# Dispenser_Scale_Feedback.net
KiCad netlist of a schematic drawn in EasyEDA Pro
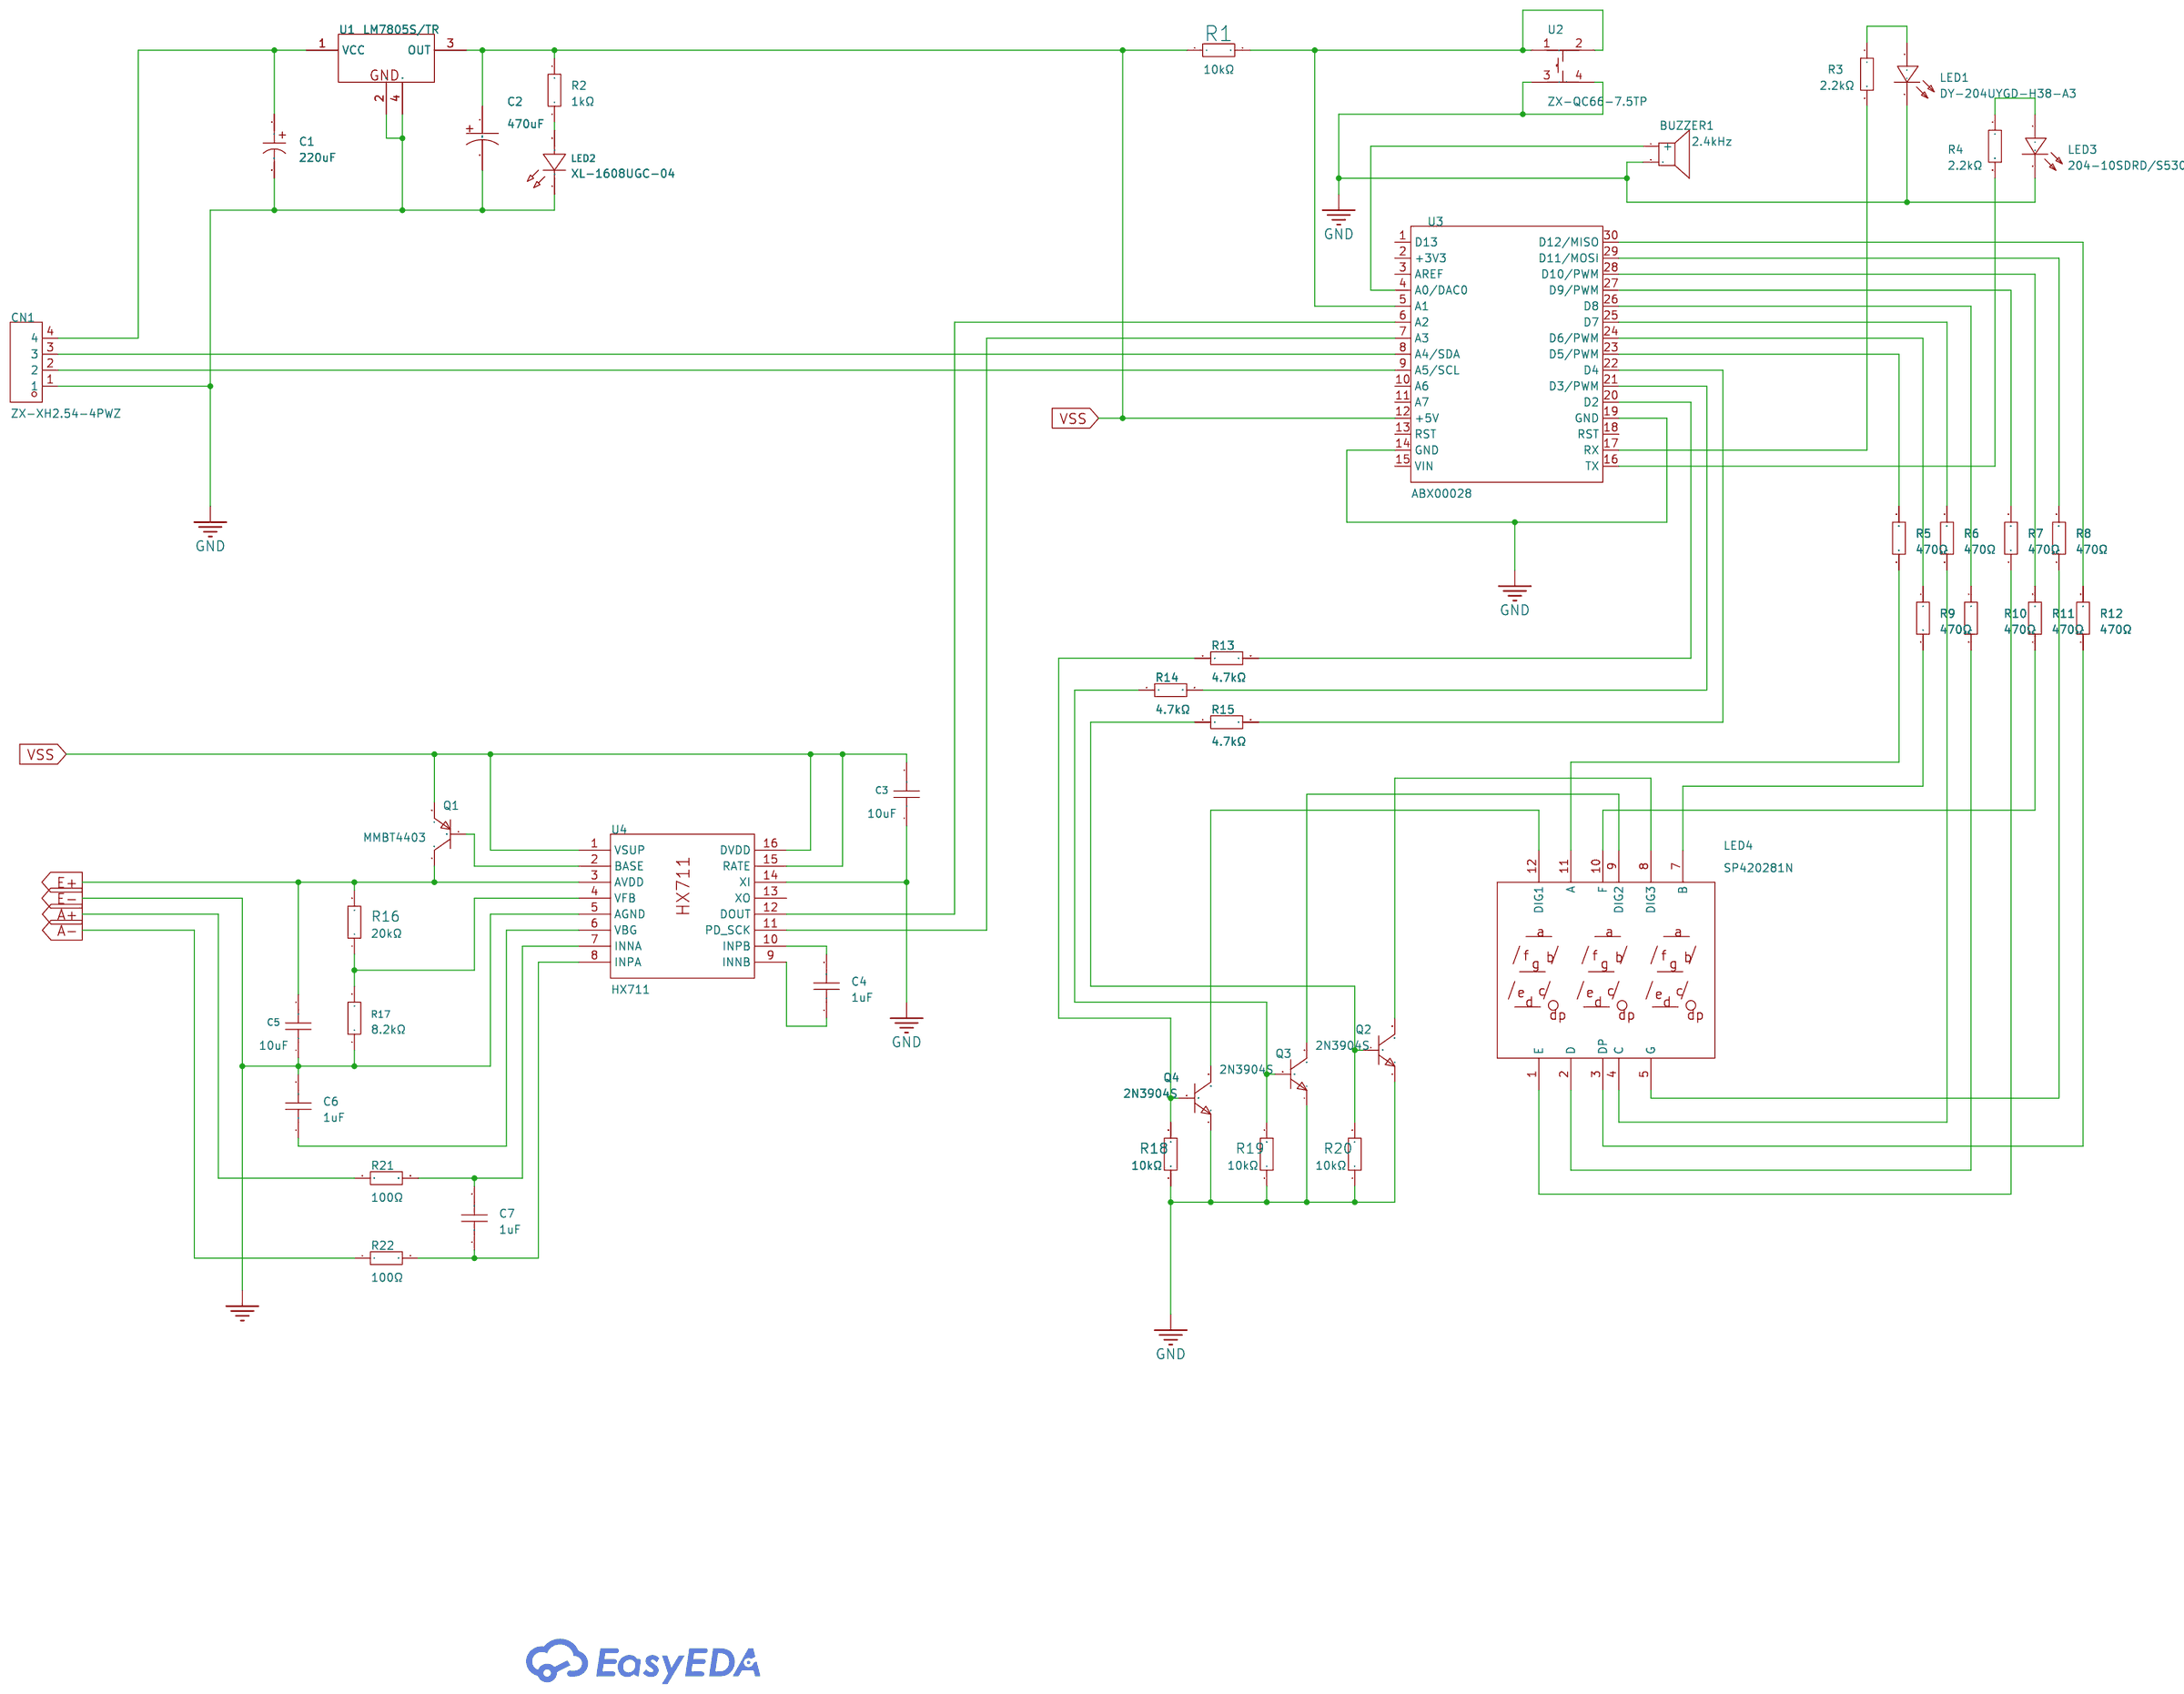
[diagram p0: schematic sheet]

(export (version "E")
  (design (tool "Eeschema 10.0.6"))
  (components
    (comp (ref "BUZZER1")
      (value "2.4kHz")
      (footprint "easyedapro:BUZ-TH_BD12.0-P7.60-D0.6-FD")
      (fields (field (name "Manufacturer Part") "TMB12A05") (field (name "Manufacturer") "华能"))
      (libsource (lib "easyedapro") (part "TMB12A05"))
    )
    (comp (ref "C1")
      (value "220uF")
      (footprint "easyedapro:CAP-SMD_BD6.3-L6.6-W6.6-LS7.4-FD")
      (fields (field (name "Manufacturer Part") "RVT1E221M0607") (field (name "Manufacturer") "ROQANG(容强)"))
      (libsource (lib "easyedapro") (part "RVT1E221M0607_C2918361"))
    )
    (comp (ref "C2")
      (value "470uF")
      (footprint "easyedapro:CAP-SMD_BD6.3-L6.6-W6.6-FD")
      (fields (field (name "Manufacturer Part") "RVT1A471M0607") (field (name "Manufacturer") "ROQANG(容强)"))
      (libsource (lib "easyedapro") (part "RVT1A471M0607_C335982"))
    )
    (comp (ref "C3")
      (value "10uF")
      (footprint "easyedapro:C0603")
      (fields
        (field (name "Manufacturer Part") "CL10A106MQ8NNNC")
        (field (name "Manufacturer") "SAMSUNG(三星)")
      )
      (libsource (lib "easyedapro") (part "CL10A106MQ8NNNC"))
    )
    (comp (ref "C4")
      (value "1uF")
      (footprint "easyedapro:C0603")
      (description "Capacitance:1uF Tolerance:±10% Tolerance:±10% Voltage Rating:50V Temperature Coefficient:X5R")
      (fields
        (field (name "Manufacturer Part") "CL10A105KB8NNNC")
        (field (name "Manufacturer") "SAMSUNG(三星)")
      )
      (libsource (lib "easyedapro") (part "CL10A105KB8NNNC"))
    )
    (comp (ref "C5")
      (value "10uF")
      (footprint "easyedapro:C0603")
      (fields
        (field (name "Manufacturer Part") "CL10A106MQ8NNNC")
        (field (name "Manufacturer") "SAMSUNG(三星)")
      )
      (libsource (lib "easyedapro") (part "CL10A106MQ8NNNC"))
    )
    (comp (ref "C6")
      (value "1uF")
      (footprint "easyedapro:C0603")
      (description "Capacitance:1uF Tolerance:±10% Tolerance:±10% Voltage Rating:50V Temperature Coefficient:X5R")
      (fields
        (field (name "Manufacturer Part") "CL10A105KB8NNNC")
        (field (name "Manufacturer") "SAMSUNG(三星)")
      )
      (libsource (lib "easyedapro") (part "CL10A105KB8NNNC"))
    )
    (comp (ref "C7")
      (value "1uF")
      (footprint "easyedapro:C0603")
      (description "Capacitance:1uF Tolerance:±10% Tolerance:±10% Voltage Rating:50V Temperature Coefficient:X5R")
      (fields
        (field (name "Manufacturer Part") "CL10A105KB8NNNC")
        (field (name "Manufacturer") "SAMSUNG(三星)")
      )
      (libsource (lib "easyedapro") (part "CL10A105KB8NNNC"))
    )
    (comp (ref "CN1")
      (value "ZX-XH2.54-4PWZ")
      (footprint "easyedapro:CONN-TH_4P-P2.50_ZX-XH2.54-4PWZ")
      (fields (field (name "Manufacturer") "Megastar(兆星)"))
      (libsource (lib "easyedapro") (part "ZX-XH2.54-4PWZ"))
    )
    (comp (ref "LED1")
      (value "DY-204UYGD-H38-A3")
      (footprint "easyedapro:LED-TH_BD4.0-P2.54-FD")
      (fields (field (name "Manufacturer") "TONYU(东裕)"))
      (libsource (lib "easyedapro") (part "DY-204UYGD-H38-A3"))
    )
    (comp (ref "LED2")
      (value "XL-1608UGC-04")
      (footprint "easyedapro:LED0603-RD_GREEN")
      (fields (field (name "Manufacturer") "XINGLIGHT(成兴光)"))
      (libsource (lib "easyedapro") (part "XL-1608UGC-04"))
    )
    (comp (ref "LED3")
      (value "204-10SDRD/S530-A3/F182-68")
      (footprint "easyedapro:LED-TH_BD4.0-P2.54-FD")
      (fields (field (name "Manufacturer") "EVERLIGHT(亿光)"))
      (libsource (lib "easyedapro") (part "DY-204UYGD-H38-A3"))
    )
    (comp (ref "LED4")
      (value "SP420281N")
      (footprint "easyedapro:LED-SEG-TH_SP420281N")
      (fields (field (name "Manufacturer") "ARKLED(方舟)"))
      (libsource (lib "easyedapro") (part "SP420281N"))
    )
    (comp (ref "Q1")
      (value "MMBT4403")
      (footprint "easyedapro:SOT-23-3_L2.9-W1.3-P1.90-LS2.4-BR")
      (fields (field (name "Manufacturer") "TWGMC(台湾迪嘉)"))
      (libsource (lib "easyedapro") (part "MMBT4403_C727134"))
    )
    (comp (ref "Q2")
      (value "2N3904S")
      (footprint "easyedapro:SOT-23-3_L2.9-W1.3-P1.90-LS2.4-TR")
      (fields (field (name "Manufacturer") "KEC"))
      (libsource (lib "easyedapro") (part "2n3904S-RTK/PS_C18536"))
    )
    (comp (ref "Q3")
      (value "2N3904S")
      (footprint "easyedapro:SOT-23-3_L2.9-W1.3-P1.90-LS2.4-TR")
      (fields (field (name "Manufacturer") "KEC"))
      (libsource (lib "easyedapro") (part "2n3904S-RTK/PS_C18536"))
    )
    (comp (ref "Q4")
      (value "2N3904S")
      (footprint "easyedapro:SOT-23-3_L2.9-W1.3-P1.90-LS2.4-TR")
      (fields (field (name "Manufacturer") "KEC"))
      (libsource (lib "easyedapro") (part "2n3904S-RTK/PS_C18536"))
    )
    (comp (ref "R1")
      (value "10kΩ")
      (footprint "easyedapro:R0603")
      (fields
        (field (name "Manufacturer Part") "0603WAF1002T5E")
        (field (name "Manufacturer") "UNI-ROYAL(厚声)")
      )
      (libsource (lib "easyedapro") (part "0603WAF1002T5E"))
    )
    (comp (ref "R2")
      (value "1kΩ")
      (footprint "easyedapro:R0603")
      (fields
        (field (name "Manufacturer Part") "0603WAF1001T5E")
        (field (name "Manufacturer") "UNI-ROYAL(厚声)")
      )
      (libsource (lib "easyedapro") (part "0603WAF1001T5E"))
    )
    (comp (ref "R3")
      (value "2.2kΩ")
      (footprint "easyedapro:R0603")
      (fields
        (field (name "Manufacturer Part") "0603WAF2201T5E")
        (field (name "Manufacturer") "UNI-ROYAL(厚声)")
      )
      (libsource (lib "easyedapro") (part "0603WAF2201T5E"))
    )
    (comp (ref "R4")
      (value "2.2kΩ")
      (footprint "easyedapro:R0603")
      (fields
        (field (name "Manufacturer Part") "0603WAF2201T5E")
        (field (name "Manufacturer") "UNI-ROYAL(厚声)")
      )
      (libsource (lib "easyedapro") (part "0603WAF2201T5E"))
    )
    (comp (ref "R5")
      (value "470Ω")
      (footprint "easyedapro:R0603")
      (fields
        (field (name "Manufacturer Part") "0603WAF4700T5E")
        (field (name "Manufacturer") "UNI-ROYAL(厚声)")
      )
      (libsource (lib "easyedapro") (part "0603WAF4700T5E"))
    )
    (comp (ref "R6")
      (value "470Ω")
      (footprint "easyedapro:R0603")
      (fields
        (field (name "Manufacturer Part") "0603WAF4700T5E")
        (field (name "Manufacturer") "UNI-ROYAL(厚声)")
      )
      (libsource (lib "easyedapro") (part "0603WAF4700T5E"))
    )
    (comp (ref "R7")
      (value "470Ω")
      (footprint "easyedapro:R0603")
      (fields
        (field (name "Manufacturer Part") "0603WAF4700T5E")
        (field (name "Manufacturer") "UNI-ROYAL(厚声)")
      )
      (libsource (lib "easyedapro") (part "0603WAF4700T5E"))
    )
    (comp (ref "R8")
      (value "470Ω")
      (footprint "easyedapro:R0603")
      (fields
        (field (name "Manufacturer Part") "0603WAF4700T5E")
        (field (name "Manufacturer") "UNI-ROYAL(厚声)")
      )
      (libsource (lib "easyedapro") (part "0603WAF4700T5E"))
    )
    (comp (ref "R9")
      (value "470Ω")
      (footprint "easyedapro:R0603")
      (fields
        (field (name "Manufacturer Part") "0603WAF4700T5E")
        (field (name "Manufacturer") "UNI-ROYAL(厚声)")
      )
      (libsource (lib "easyedapro") (part "0603WAF4700T5E"))
    )
    (comp (ref "R10")
      (value "470Ω")
      (footprint "easyedapro:R0603")
      (fields
        (field (name "Manufacturer Part") "0603WAF4700T5E")
        (field (name "Manufacturer") "UNI-ROYAL(厚声)")
      )
      (libsource (lib "easyedapro") (part "0603WAF4700T5E"))
    )
    (comp (ref "R11")
      (value "470Ω")
      (footprint "easyedapro:R0603")
      (fields
        (field (name "Manufacturer Part") "0603WAF4700T5E")
        (field (name "Manufacturer") "UNI-ROYAL(厚声)")
      )
      (libsource (lib "easyedapro") (part "0603WAF4700T5E"))
    )
    (comp (ref "R12")
      (value "470Ω")
      (footprint "easyedapro:R0603")
      (fields
        (field (name "Manufacturer Part") "0603WAF4700T5E")
        (field (name "Manufacturer") "UNI-ROYAL(厚声)")
      )
      (libsource (lib "easyedapro") (part "0603WAF4700T5E"))
    )
    (comp (ref "R13")
      (value "4.7kΩ")
      (footprint "easyedapro:R0603")
      (fields
        (field (name "Manufacturer Part") "0603WAF4701T5E")
        (field (name "Manufacturer") "UNI-ROYAL(厚声)")
      )
      (libsource (lib "easyedapro") (part "0603WAF4701T5E"))
    )
    (comp (ref "R14")
      (value "4.7kΩ")
      (footprint "easyedapro:R0603")
      (fields
        (field (name "Manufacturer Part") "0603WAF4701T5E")
        (field (name "Manufacturer") "UNI-ROYAL(厚声)")
      )
      (libsource (lib "easyedapro") (part "0603WAF4701T5E"))
    )
    (comp (ref "R15")
      (value "4.7kΩ")
      (footprint "easyedapro:R0603")
      (fields
        (field (name "Manufacturer Part") "0603WAF4701T5E")
        (field (name "Manufacturer") "UNI-ROYAL(厚声)")
      )
      (libsource (lib "easyedapro") (part "0603WAF4701T5E"))
    )
    (comp (ref "R16")
      (value "20kΩ")
      (footprint "easyedapro:R0603")
      (fields
        (field (name "Manufacturer Part") "0603WAF2002T5E")
        (field (name "Manufacturer") "UNI-ROYAL(厚声)")
      )
      (libsource (lib "easyedapro") (part "0603WAF2002T5E"))
    )
    (comp (ref "R17")
      (value "8.2kΩ")
      (footprint "easyedapro:R0603")
      (fields
        (field (name "Manufacturer Part") "0603WAF8201T5E")
        (field (name "Manufacturer") "UNI-ROYAL(厚声)")
      )
      (libsource (lib "easyedapro") (part "0603WAF8201T5E"))
    )
    (comp (ref "R18")
      (value "10kΩ")
      (footprint "easyedapro:R0603")
      (fields
        (field (name "Manufacturer Part") "0603WAF1002T5E")
        (field (name "Manufacturer") "UNI-ROYAL(厚声)")
      )
      (libsource (lib "easyedapro") (part "0603WAF1002T5E"))
    )
    (comp (ref "R19")
      (value "10kΩ")
      (footprint "easyedapro:R0603")
      (fields
        (field (name "Manufacturer Part") "0603WAF1002T5E")
        (field (name "Manufacturer") "UNI-ROYAL(厚声)")
      )
      (libsource (lib "easyedapro") (part "0603WAF1002T5E"))
    )
    (comp (ref "R20")
      (value "10kΩ")
      (footprint "easyedapro:R0603")
      (fields
        (field (name "Manufacturer Part") "0603WAF1002T5E")
        (field (name "Manufacturer") "UNI-ROYAL(厚声)")
      )
      (libsource (lib "easyedapro") (part "0603WAF1002T5E"))
    )
    (comp (ref "R21")
      (value "100Ω")
      (footprint "easyedapro:R0603")
      (fields
        (field (name "Manufacturer Part") "0603WAF1000T5E")
        (field (name "Manufacturer") "UNI-ROYAL(厚声)")
      )
      (libsource (lib "easyedapro") (part "0603WAF1000T5E"))
    )
    (comp (ref "R22")
      (value "100Ω")
      (footprint "easyedapro:R0603")
      (fields
        (field (name "Manufacturer Part") "0603WAF1000T5E")
        (field (name "Manufacturer") "UNI-ROYAL(厚声)")
      )
      (libsource (lib "easyedapro") (part "0603WAF1000T5E"))
    )
    (comp (ref "U1")
      (value "LM7805S/TR")
      (footprint "easyedapro:TO-263-3_L8.6-W10.2-P2.54-LS14.4-BR")
      (description "Output Type:-")
      (fields (field (name "Manufacturer") "HGSEMI(华冠)"))
      (libsource (lib "easyedapro") (part "LM7805S/TR"))
    )
    (comp (ref "U2")
      (value "ZX-QC66-7.5TP")
      (footprint "easyedapro:KEY-SMD_4P-L6.0-W6.0-P4.50-LS8.6")
      (fields (field (name "Manufacturer") "Megastar(兆星)"))
      (libsource (lib "easyedapro") (part "ZX-QC66-7.5TP"))
    )
    (comp (ref "U3")
      (value "ABX00028")
      (footprint "easyedapro:MOD-TH_ABX00028")
      (fields (field (name "Manufacturer") "arduino"))
      (libsource (lib "easyedapro") (part "ABX00028"))
    )
    (comp (ref "U4")
      (value "HX711")
      (footprint "easyedapro:SOP-16_L10.0-W3.9-P1.27-LS6.0-BL")
      (fields (field (name "Manufacturer") "AVIA(海芯科技)"))
      (libsource (lib "easyedapro") (part "HX711"))
    )
  )
  (nets
    (net (code "1") (name "A+") (class "Default")
      (node (ref "R21") (pin "1") (pinfunction "1_1") (pintype "input"))
    )
    (net (code "2") (name "A-") (class "Default")
      (node (ref "R22") (pin "1") (pinfunction "1_1") (pintype "input"))
    )
    (net (code "3") (name "E+") (class "Default")
      (node (ref "C5") (pin "2") (pinfunction "2_2") (pintype "input"))
      (node (ref "Q1") (pin "3") (pinfunction "C_3") (pintype "input"))
      (node (ref "R16") (pin "2") (pinfunction "2_2") (pintype "input"))
      (node (ref "U4") (pin "3") (pinfunction "AVDD_3") (pintype "unspecified"))
    )
    (net (code "4") (name "E-") (class "Default")
      (node (ref "C5") (pin "1") (pinfunction "1_1") (pintype "input"))
      (node (ref "C6") (pin "2") (pinfunction "2_2") (pintype "unspecified"))
      (node (ref "R17") (pin "1") (pinfunction "1_1") (pintype "input"))
      (node (ref "U4") (pin "5") (pinfunction "AGND_5") (pintype "unspecified"))
    )
    (net (code "5") (name "GND") (class "Default")
      (node (ref "BUZZER1") (pin "2") (pinfunction "2_2") (pintype "unspecified"))
      (node (ref "C1") (pin "2") (pinfunction "2_2") (pintype "input"))
      (node (ref "C2") (pin "2") (pinfunction "2_2") (pintype "unspecified"))
      (node (ref "C3") (pin "1") (pinfunction "1_1") (pintype "input"))
      (node (ref "CN1") (pin "1") (pinfunction "1_1") (pintype "unspecified"))
      (node (ref "LED1") (pin "2") (pinfunction "K_2") (pintype "unspecified"))
      (node (ref "LED2") (pin "1") (pinfunction "K_1") (pintype "input"))
      (node (ref "LED3") (pin "2") (pinfunction "K_2") (pintype "unspecified"))
      (node (ref "Q2") (pin "1") (pinfunction "E_1") (pintype "input"))
      (node (ref "Q3") (pin "1") (pinfunction "E_1") (pintype "input"))
      (node (ref "Q4") (pin "1") (pinfunction "E_1") (pintype "input"))
      (node (ref "R18") (pin "1") (pinfunction "1_1") (pintype "input"))
      (node (ref "R19") (pin "1") (pinfunction "1_1") (pintype "input"))
      (node (ref "R20") (pin "1") (pinfunction "1_1") (pintype "input"))
      (node (ref "U1") (pin "2") (pinfunction "GND_2") (pintype "input"))
      (node (ref "U1") (pin "4") (pinfunction "GND_4") (pintype "input"))
      (node (ref "U2") (pin "3") (pinfunction "3_3") (pintype "unspecified"))
      (node (ref "U2") (pin "4") (pinfunction "4_4") (pintype "unspecified"))
      (node (ref "U3") (pin "14") (pinfunction "GND_14") (pintype "unspecified"))
      (node (ref "U3") (pin "19") (pinfunction "GND_19") (pintype "unspecified"))
      (node (ref "U4") (pin "14") (pinfunction "XI_14") (pintype "unspecified"))
    )
    (net (code "6") (name "Net-(BUZZER1-+)") (class "Default")
      (node (ref "BUZZER1") (pin "1") (pinfunction "+_1") (pintype "unspecified"))
      (node (ref "U3") (pin "4") (pinfunction "A0/DAC0_4") (pintype "unspecified"))
    )
    (net (code "7") (name "Net-(LED1-A)") (class "Default")
      (node (ref "LED1") (pin "1") (pinfunction "A_1") (pintype "unspecified"))
      (node (ref "R3") (pin "1") (pinfunction "1_1") (pintype "input"))
    )
    (net (code "8") (name "Net-(LED2-A)") (class "Default")
      (node (ref "LED2") (pin "2") (pinfunction "A_2") (pintype "input"))
      (node (ref "R2") (pin "1") (pinfunction "1_1") (pintype "input"))
    )
    (net (code "9") (name "Net-(LED3-A)") (class "Default")
      (node (ref "LED3") (pin "1") (pinfunction "A_1") (pintype "unspecified"))
      (node (ref "R4") (pin "1") (pinfunction "1_1") (pintype "input"))
    )
    (net (code "10") (name "Net-(LED4-A)") (class "Default")
      (node (ref "LED4") (pin "11") (pinfunction "A_11") (pintype "input"))
      (node (ref "R5") (pin "1") (pinfunction "1_1") (pintype "input"))
    )
    (net (code "11") (name "Net-(LED4-B)") (class "Default")
      (node (ref "LED4") (pin "7") (pinfunction "B_7") (pintype "input"))
      (node (ref "R9") (pin "2") (pinfunction "2_2") (pintype "input"))
    )
    (net (code "12") (name "Net-(LED4-C)") (class "Default")
      (node (ref "LED4") (pin "4") (pinfunction "C_4") (pintype "input"))
      (node (ref "R6") (pin "1") (pinfunction "1_1") (pintype "input"))
    )
    (net (code "13") (name "Net-(LED4-D)") (class "Default")
      (node (ref "LED4") (pin "2") (pinfunction "D_2") (pintype "input"))
      (node (ref "R10") (pin "2") (pinfunction "2_2") (pintype "input"))
    )
    (net (code "14") (name "Net-(LED4-DIG1)") (class "Default")
      (node (ref "LED4") (pin "12") (pinfunction "DIG1_12") (pintype "input"))
      (node (ref "Q4") (pin "3") (pinfunction "C_3") (pintype "input"))
    )
    (net (code "15") (name "Net-(LED4-DIG2)") (class "Default")
      (node (ref "LED4") (pin "9") (pinfunction "DIG2_9") (pintype "input"))
      (node (ref "Q3") (pin "3") (pinfunction "C_3") (pintype "input"))
    )
    (net (code "16") (name "Net-(LED4-DIG3)") (class "Default")
      (node (ref "LED4") (pin "8") (pinfunction "DIG3_8") (pintype "input"))
      (node (ref "Q2") (pin "3") (pinfunction "C_3") (pintype "input"))
    )
    (net (code "17") (name "Net-(LED4-DP)") (class "Default")
      (node (ref "LED4") (pin "3") (pinfunction "DP_3") (pintype "input"))
      (node (ref "R12") (pin "1") (pinfunction "1_1") (pintype "input"))
    )
    (net (code "18") (name "Net-(LED4-E)") (class "Default")
      (node (ref "LED4") (pin "1") (pinfunction "E_1") (pintype "input"))
      (node (ref "R7") (pin "1") (pinfunction "1_1") (pintype "input"))
    )
    (net (code "19") (name "Net-(LED4-F)") (class "Default")
      (node (ref "LED4") (pin "10") (pinfunction "F_10") (pintype "input"))
      (node (ref "R11") (pin "1") (pinfunction "1_1") (pintype "input"))
    )
    (net (code "20") (name "Net-(LED4-G)") (class "Default")
      (node (ref "LED4") (pin "5") (pinfunction "G_5") (pintype "input"))
      (node (ref "R8") (pin "1") (pinfunction "1_1") (pintype "input"))
    )
    (net (code "21") (name "Net-(Q1-B)") (class "Default")
      (node (ref "Q1") (pin "1") (pinfunction "B_1") (pintype "input"))
      (node (ref "U4") (pin "2") (pinfunction "BASE_2") (pintype "unspecified"))
    )
    (net (code "22") (name "Net-(Q2-B)") (class "Default")
      (node (ref "Q2") (pin "2") (pinfunction "B_2") (pintype "input"))
      (node (ref "R15") (pin "1") (pinfunction "1_1") (pintype "input"))
      (node (ref "R20") (pin "2") (pinfunction "2_2") (pintype "input"))
    )
    (net (code "23") (name "Net-(Q3-B)") (class "Default")
      (node (ref "Q3") (pin "2") (pinfunction "B_2") (pintype "input"))
      (node (ref "R14") (pin "1") (pinfunction "1_1") (pintype "input"))
      (node (ref "R19") (pin "2") (pinfunction "2_2") (pintype "input"))
    )
    (net (code "24") (name "Net-(Q4-B)") (class "Default")
      (node (ref "Q4") (pin "2") (pinfunction "B_2") (pintype "input"))
      (node (ref "R13") (pin "1") (pinfunction "1_1") (pintype "input"))
      (node (ref "R18") (pin "2") (pinfunction "2_2") (pintype "input"))
    )
    (net (code "25") (name "Net-(U1-VCC)") (class "Default")
      (node (ref "C1") (pin "1") (pinfunction "1_1") (pintype "input"))
      (node (ref "CN1") (pin "4") (pinfunction "4_4") (pintype "unspecified"))
      (node (ref "U1") (pin "1") (pinfunction "VCC_1") (pintype "input"))
    )
    (net (code "26") (name "Net-(U3-A1)") (class "Default")
      (node (ref "R1") (pin "2") (pinfunction "2_2") (pintype "input"))
      (node (ref "U2") (pin "1") (pinfunction "1_1") (pintype "unspecified"))
      (node (ref "U2") (pin "2") (pinfunction "2_2") (pintype "unspecified"))
      (node (ref "U3") (pin "5") (pinfunction "A1_5") (pintype "unspecified"))
    )
    (net (code "27") (name "Net-(U3-A2)") (class "Default")
      (node (ref "U3") (pin "6") (pinfunction "A2_6") (pintype "unspecified"))
      (node (ref "U4") (pin "12") (pinfunction "DOUT_12") (pintype "unspecified"))
    )
    (net (code "28") (name "Net-(U3-A3)") (class "Default")
      (node (ref "U3") (pin "7") (pinfunction "A3_7") (pintype "unspecified"))
      (node (ref "U4") (pin "11") (pinfunction "PD_SCK_11") (pintype "unspecified"))
    )
    (net (code "29") (name "Net-(U3-A4{slash}SDA)") (class "Default")
      (node (ref "CN1") (pin "3") (pinfunction "3_3") (pintype "unspecified"))
      (node (ref "U3") (pin "8") (pinfunction "A4/SDA_8") (pintype "unspecified"))
    )
    (net (code "30") (name "Net-(U3-A5{slash}SCL)") (class "Default")
      (node (ref "CN1") (pin "2") (pinfunction "2_2") (pintype "unspecified"))
      (node (ref "U3") (pin "9") (pinfunction "A5/SCL_9") (pintype "unspecified"))
    )
    (net (code "31") (name "Net-(U3-D2)") (class "Default")
      (node (ref "R13") (pin "2") (pinfunction "2_2") (pintype "input"))
      (node (ref "U3") (pin "20") (pinfunction "D2_20") (pintype "unspecified"))
    )
    (net (code "32") (name "Net-(U3-D3{slash}PWM)") (class "Default")
      (node (ref "R14") (pin "2") (pinfunction "2_2") (pintype "input"))
      (node (ref "U3") (pin "21") (pinfunction "D3/PWM_21") (pintype "unspecified"))
    )
    (net (code "33") (name "Net-(U3-D4)") (class "Default")
      (node (ref "R15") (pin "2") (pinfunction "2_2") (pintype "input"))
      (node (ref "U3") (pin "22") (pinfunction "D4_22") (pintype "unspecified"))
    )
    (net (code "34") (name "Net-(U3-D5{slash}PWM)") (class "Default")
      (node (ref "R5") (pin "2") (pinfunction "2_2") (pintype "input"))
      (node (ref "U3") (pin "23") (pinfunction "D5/PWM_23") (pintype "unspecified"))
    )
    (net (code "35") (name "Net-(U3-D6{slash}PWM)") (class "Default")
      (node (ref "R9") (pin "1") (pinfunction "1_1") (pintype "input"))
      (node (ref "U3") (pin "24") (pinfunction "D6/PWM_24") (pintype "unspecified"))
    )
    (net (code "36") (name "Net-(U3-D7)") (class "Default")
      (node (ref "R6") (pin "2") (pinfunction "2_2") (pintype "input"))
      (node (ref "U3") (pin "25") (pinfunction "D7_25") (pintype "unspecified"))
    )
    (net (code "37") (name "Net-(U3-D8)") (class "Default")
      (node (ref "R10") (pin "1") (pinfunction "1_1") (pintype "input"))
      (node (ref "U3") (pin "26") (pinfunction "D8_26") (pintype "unspecified"))
    )
    (net (code "38") (name "Net-(U3-D9{slash}PWM)") (class "Default")
      (node (ref "R7") (pin "2") (pinfunction "2_2") (pintype "input"))
      (node (ref "U3") (pin "27") (pinfunction "D9/PWM_27") (pintype "unspecified"))
    )
    (net (code "39") (name "Net-(U3-D10{slash}PWM)") (class "Default")
      (node (ref "R11") (pin "2") (pinfunction "2_2") (pintype "input"))
      (node (ref "U3") (pin "28") (pinfunction "D10/PWM_28") (pintype "unspecified"))
    )
    (net (code "40") (name "Net-(U3-D11{slash}MOSI)") (class "Default")
      (node (ref "R8") (pin "2") (pinfunction "2_2") (pintype "input"))
      (node (ref "U3") (pin "29") (pinfunction "D11/MOSI_29") (pintype "unspecified"))
    )
    (net (code "41") (name "Net-(U3-D12{slash}MISO)") (class "Default")
      (node (ref "R12") (pin "2") (pinfunction "2_2") (pintype "input"))
      (node (ref "U3") (pin "30") (pinfunction "D12/MISO_30") (pintype "unspecified"))
    )
    (net (code "42") (name "Net-(U3-RX)") (class "Default")
      (node (ref "R3") (pin "2") (pinfunction "2_2") (pintype "input"))
      (node (ref "U3") (pin "17") (pinfunction "RX_17") (pintype "unspecified"))
    )
    (net (code "43") (name "Net-(U3-TX)") (class "Default")
      (node (ref "R4") (pin "2") (pinfunction "2_2") (pintype "input"))
      (node (ref "U3") (pin "16") (pinfunction "TX_16") (pintype "unspecified"))
    )
    (net (code "44") (name "Net-(U4-INNA)") (class "Default")
      (node (ref "C7") (pin "2") (pinfunction "2_2") (pintype "unspecified"))
      (node (ref "R21") (pin "2") (pinfunction "2_2") (pintype "input"))
      (node (ref "U4") (pin "7") (pinfunction "INNA_7") (pintype "unspecified"))
    )
    (net (code "45") (name "Net-(U4-INNB)") (class "Default")
      (node (ref "C4") (pin "1") (pinfunction "1_1") (pintype "unspecified"))
      (node (ref "U4") (pin "9") (pinfunction "INNB_9") (pintype "unspecified"))
    )
    (net (code "46") (name "Net-(U4-INPA)") (class "Default")
      (node (ref "C7") (pin "1") (pinfunction "1_1") (pintype "unspecified"))
      (node (ref "R22") (pin "2") (pinfunction "2_2") (pintype "input"))
      (node (ref "U4") (pin "8") (pinfunction "INPA_8") (pintype "unspecified"))
    )
    (net (code "47") (name "Net-(U4-INPB)") (class "Default")
      (node (ref "C4") (pin "2") (pinfunction "2_2") (pintype "unspecified"))
      (node (ref "U4") (pin "10") (pinfunction "INPB_10") (pintype "unspecified"))
    )
    (net (code "48") (name "Net-(U4-VBG)") (class "Default")
      (node (ref "C6") (pin "1") (pinfunction "1_1") (pintype "unspecified"))
      (node (ref "U4") (pin "6") (pinfunction "VBG_6") (pintype "unspecified"))
    )
    (net (code "49") (name "Net-(U4-VFB)") (class "Default")
      (node (ref "R16") (pin "1") (pinfunction "1_1") (pintype "input"))
      (node (ref "R17") (pin "2") (pinfunction "2_2") (pintype "input"))
      (node (ref "U4") (pin "4") (pinfunction "VFB_4") (pintype "unspecified"))
    )
    (net (code "50") (name "VSS") (class "Default")
      (node (ref "C2") (pin "1") (pinfunction "1_1") (pintype "unspecified"))
      (node (ref "C3") (pin "2") (pinfunction "2_2") (pintype "input"))
      (node (ref "Q1") (pin "2") (pinfunction "E_2") (pintype "input"))
      (node (ref "R1") (pin "1") (pinfunction "1_1") (pintype "input"))
      (node (ref "R2") (pin "2") (pinfunction "2_2") (pintype "input"))
      (node (ref "U1") (pin "3") (pinfunction "OUT_3") (pintype "input"))
      (node (ref "U3") (pin "12") (pinfunction "+5V_12") (pintype "unspecified"))
      (node (ref "U4") (pin "1") (pinfunction "VSUP_1") (pintype "unspecified"))
      (node (ref "U4") (pin "15") (pinfunction "RATE_15") (pintype "unspecified"))
      (node (ref "U4") (pin "16") (pinfunction "DVDD_16") (pintype "unspecified"))
    )
    (net (code "51") (name "unconnected-(U3-+3V3-Pad2)") (class "Default")
      (node (ref "U3") (pin "2") (pinfunction "+3V3_2") (pintype "unspecified"))
    )
    (net (code "52") (name "unconnected-(U3-A6-Pad10)") (class "Default")
      (node (ref "U3") (pin "10") (pinfunction "A6_10") (pintype "unspecified"))
    )
    (net (code "53") (name "unconnected-(U3-A7-Pad11)") (class "Default")
      (node (ref "U3") (pin "11") (pinfunction "A7_11") (pintype "unspecified"))
    )
    (net (code "54") (name "unconnected-(U3-AREF-Pad3)") (class "Default")
      (node (ref "U3") (pin "3") (pinfunction "AREF_3") (pintype "unspecified"))
    )
    (net (code "55") (name "unconnected-(U3-D13-Pad1)") (class "Default")
      (node (ref "U3") (pin "1") (pinfunction "D13_1") (pintype "unspecified"))
    )
    (net (code "56") (name "unconnected-(U3-RST-Pad13)") (class "Default")
      (node (ref "U3") (pin "13") (pinfunction "RST_13") (pintype "unspecified"))
    )
    (net (code "57") (name "unconnected-(U3-RST-Pad18)") (class "Default")
      (node (ref "U3") (pin "18") (pinfunction "RST_18") (pintype "unspecified"))
    )
    (net (code "58") (name "unconnected-(U3-VIN-Pad15)") (class "Default")
      (node (ref "U3") (pin "15") (pinfunction "VIN_15") (pintype "unspecified"))
    )
    (net (code "59") (name "unconnected-(U4-XO-Pad13)") (class "Default")
      (node (ref "U4") (pin "13") (pinfunction "XO_13") (pintype "unspecified"))
    )
  )
)
